# OPID_352_3_3V_Step-down_regulator.net
KiCad netlist of a schematic drawn in Altium Designer
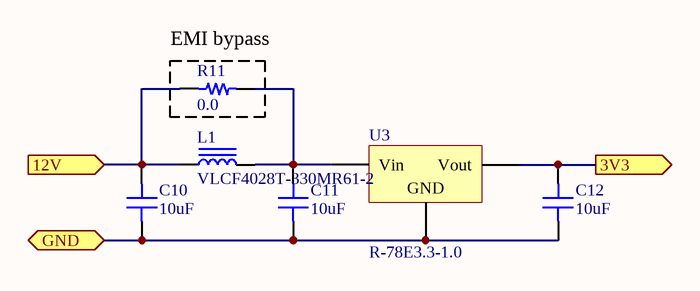
[diagram p0: OPID[352] 3.3V Step-down regulator.SchDoc]

(export (version "E")
  (design (tool "Eeschema 10.0.6"))
  (components
    (comp (ref "C10")
      (value "10uF")
      (footprint "CAP 1210/3225 - 2.8MM")
      (description "CAP CER 10UF 50V X7S 1210")
      (fields
        (field (name "PART NUMBER") "C3225X7S1H106M250AB")
        (field (name "MANUFACTURER") "TDK Corporation")
      )
      (libsource (lib "Celestial Library Database") (part "Capacitor"))
    )
    (comp (ref "C11")
      (value "10uF")
      (footprint "CAP 1210/3225 - 2.8MM")
      (description "CAP CER 10UF 50V X7S 1210")
      (fields
        (field (name "PART NUMBER") "C3225X7S1H106M250AB")
        (field (name "MANUFACTURER") "TDK Corporation")
      )
      (libsource (lib "Celestial Library Database") (part "Capacitor"))
    )
    (comp (ref "C12")
      (value "10uF")
      (footprint "CAP 1210/3225 - 2.8MM")
      (description "CAP CER 10UF 50V X7S 1210")
      (fields
        (field (name "PART NUMBER") "C3225X7S1H106M250AB")
        (field (name "MANUFACTURER") "TDK Corporation")
      )
      (libsource (lib "Celestial Library Database") (part "Capacitor"))
    )
    (comp (ref "L1")
      (value "VLCF4028T-330MR61-2")
      (footprint "TDK VLCF4028-2")
      (description "FIXED IND 33UH 610MA 350 MOHM")
      (fields (field (name "MANUFACTURER") "TDK Corporation") (field (name "TOLERANCE") "20%"))
      (libsource (lib "Celestial Library Database") (part "Inductor"))
    )
    (comp (ref "R11")
      (value "0.0")
      (footprint "RES 0805/2012")
      (description "RES SMD 0.0 OHM JUMPER 1/2W 0805")
      (fields (field (name "PART NUMBER") "5106") (field (name "MANUFACTURER") "Keystone Electronics"))
      (libsource (lib "Celestial Library Database") (part "Resistor"))
    )
    (comp (ref "U3")
      (value "R-78E3.3-1.0")
      (footprint "R-78Exx-1.0")
      (libsource (lib "Vortex-component-database") (part "Volt_Reg"))
    )
  )
  (nets
    (net (code "1") (name "/3V3") (class "Default")
      (node (ref "C12") (pin "2") (pinfunction "2_2") (pintype "passive"))
      (node (ref "U3") (pin "3") (pinfunction "Vout_3") (pintype "passive"))
    )
    (net (code "2") (name "/12V") (class "Default")
      (node (ref "C10") (pin "2") (pinfunction "2_2") (pintype "passive"))
      (node (ref "L1") (pin "1") (pinfunction "1_1") (pintype "passive"))
      (node (ref "R11") (pin "1") (pinfunction "1_1") (pintype "passive"))
    )
    (net (code "3") (name "/GND") (class "Default")
      (node (ref "C10") (pin "1") (pinfunction "1_1") (pintype "passive"))
      (node (ref "C11") (pin "1") (pinfunction "1_1") (pintype "passive"))
      (node (ref "C12") (pin "1") (pinfunction "1_1") (pintype "passive"))
      (node (ref "U3") (pin "2") (pinfunction "GND_2") (pintype "passive"))
    )
    (net (code "4") (name "Net-(U3-Vin)") (class "Default")
      (node (ref "C11") (pin "2") (pinfunction "2_2") (pintype "passive"))
      (node (ref "L1") (pin "2") (pinfunction "2_2") (pintype "passive"))
      (node (ref "R11") (pin "2") (pinfunction "2_2") (pintype "passive"))
      (node (ref "U3") (pin "1") (pinfunction "Vin_1") (pintype "passive"))
    )
  )
)
